# RK3399_Side_of_LPDDR4_Controller.net
KiCad netlist of a schematic drawn in Altium Designer
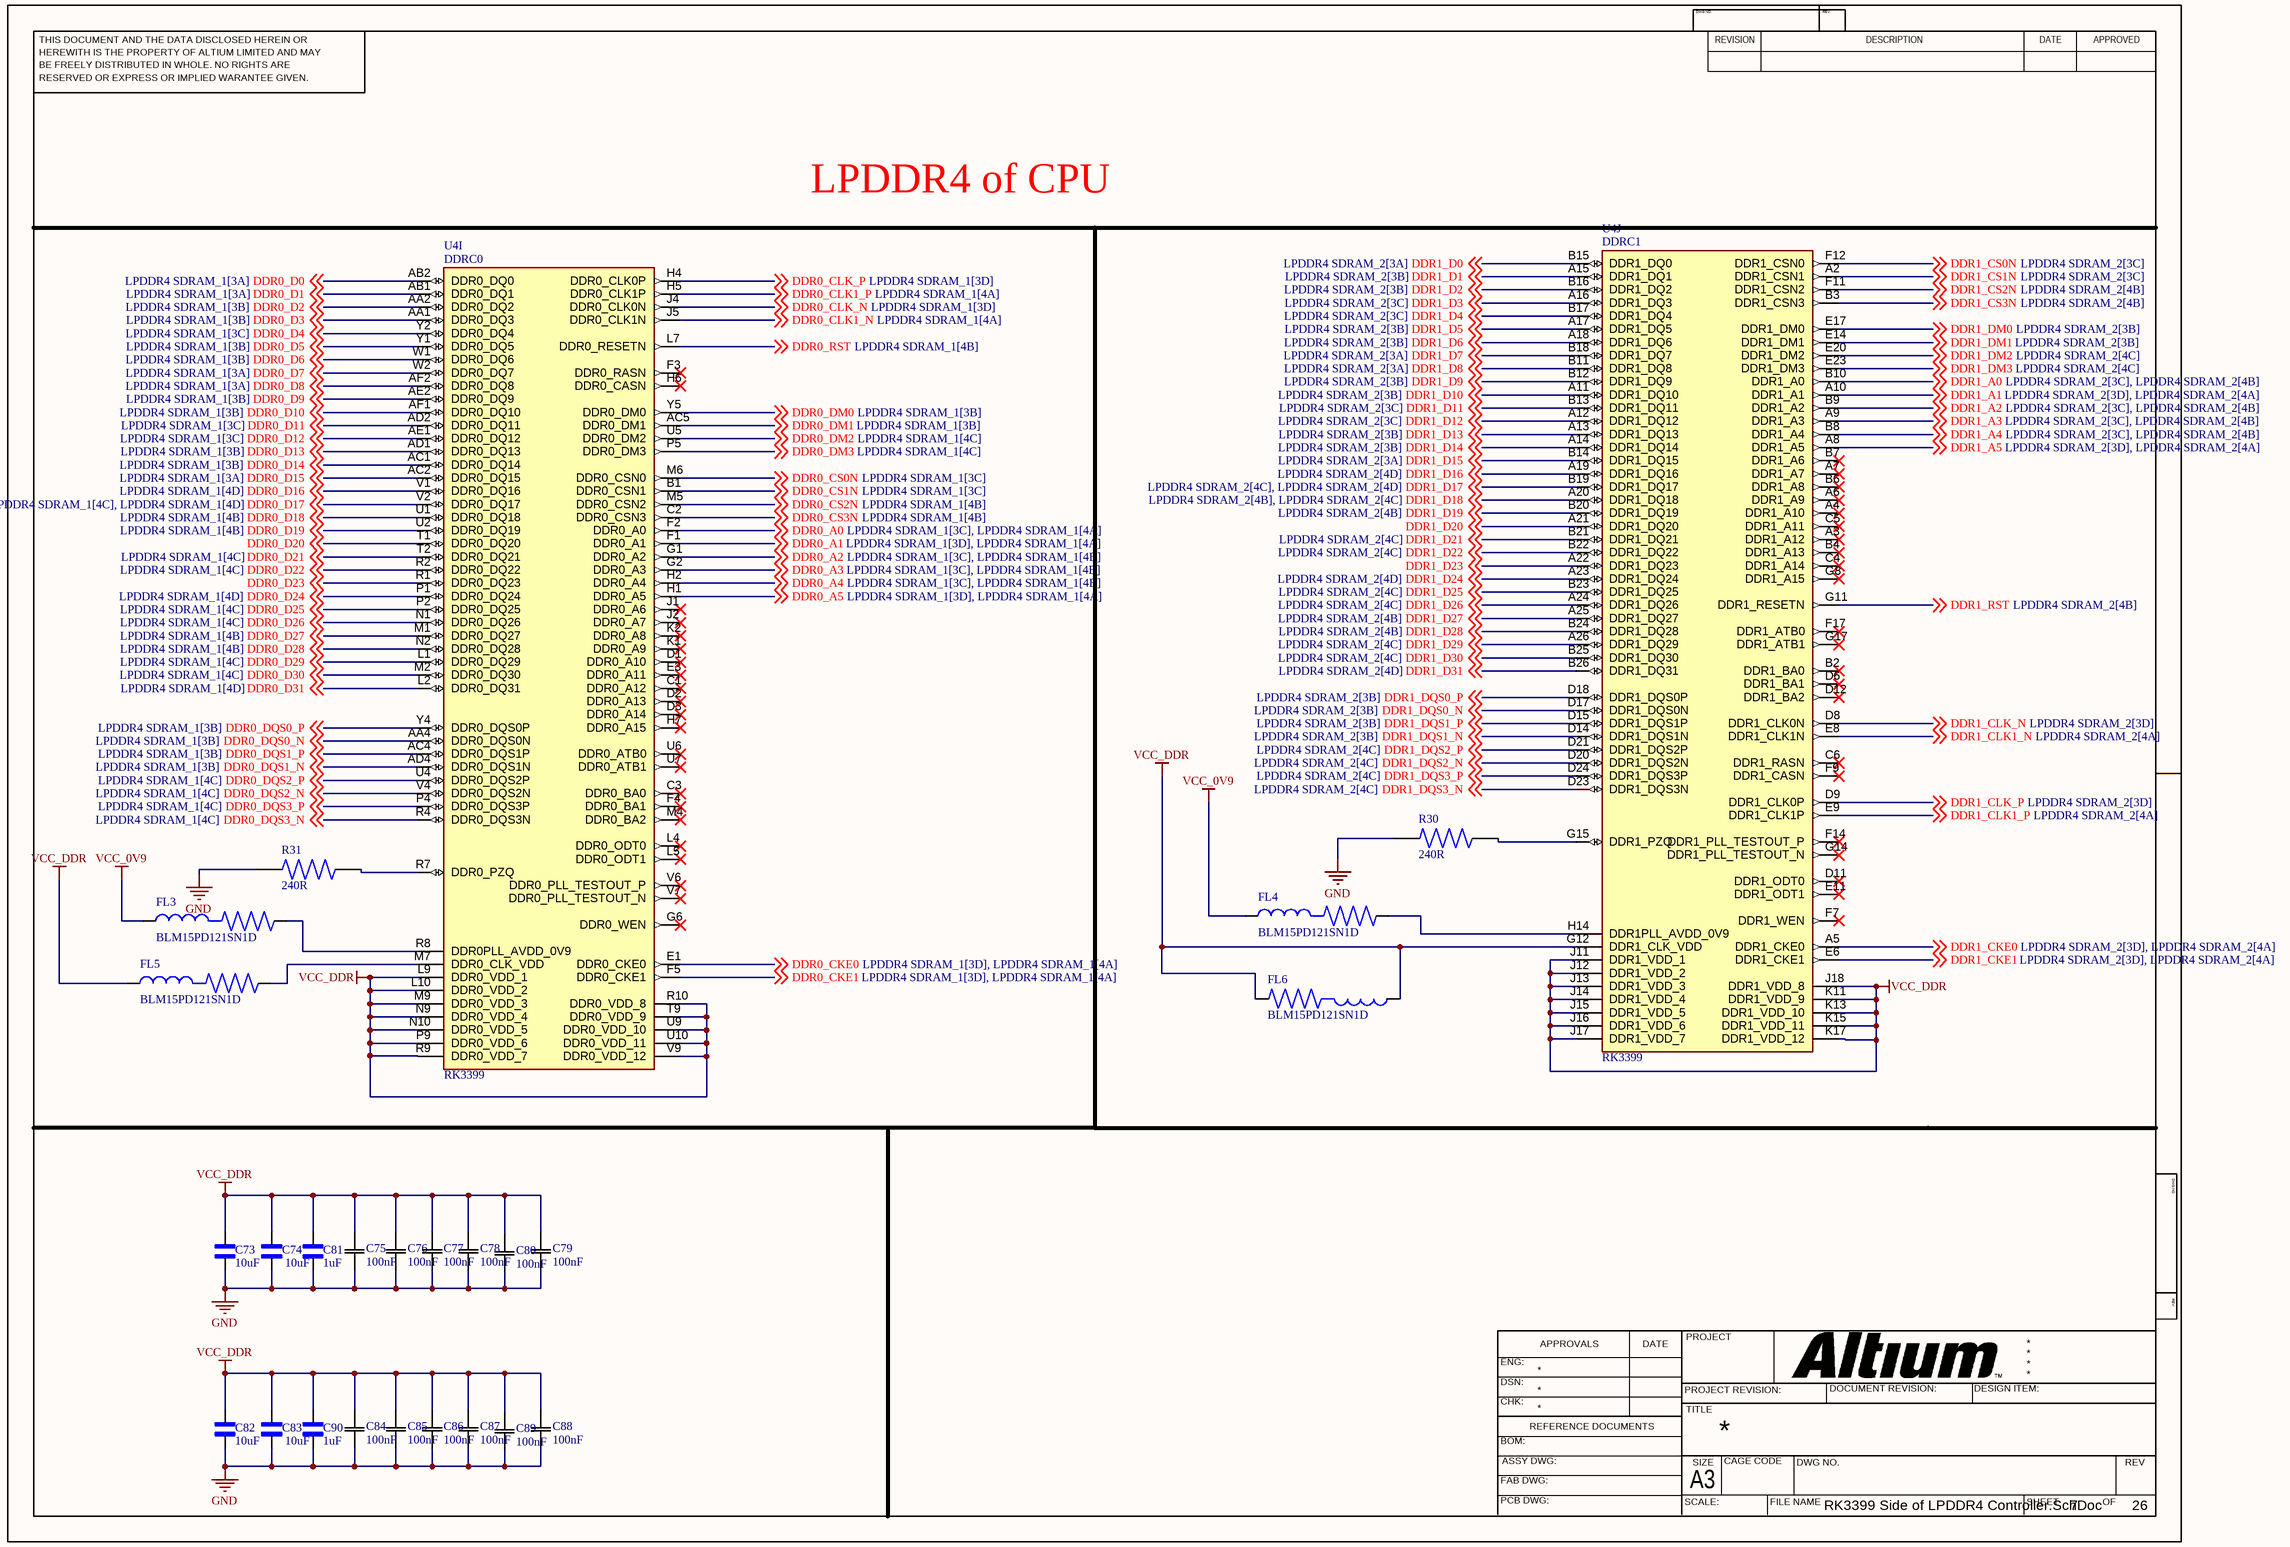
[diagram p0: RK3399 Side of LPDDR4 Controller.SchDoc]

(export (version "E")
  (design (tool "Eeschema 10.0.6"))
  (components
    (comp (ref "C73")
      (value "10uF")
      (footprint "CAPC1005X71N")
      (description "22 ÂµF Â±20% 6.3V Ceramic Capacitor X5R 0402 (1005 Metric)")
      (fields (field (name "MF") "AVX") (field (name "MP") "04026D226MAT2A"))
      (libsource (lib "04026D226MAT2A") (part "04026D226MAT2A"))
    )
    (comp (ref "C74")
      (value "10uF")
      (footprint "CAPC1005X70N")
      (description "10 ÂµF Â±20% 6.3V Ceramic Capacitor X5R 0402 (1005 Metric)")
      (fields (field (name "MF") "Samsung") (field (name "MP") "CL05A106MQ5NUNC"))
      (libsource (lib "CL05A106MQ5NUNC") (part "CL05A106MQ5NUNC"))
    )
    (comp (ref "C75")
      (value "100nF")
      (footprint "CAP_1005_TDK")
      (description "Description")
      (fields
        (field (name "MANUFACTURER_PART_NUMBER") "C1005X7R1H104M050BB")
        (field (name "COPYRIGHT") "Copyright (C) 2025 Ultra Librarian. All rights reserved.")
      )
      (libsource (lib "C1005X7R1H104M050BB") (part "C1005X7R1H104M050BB"))
    )
    (comp (ref "C76")
      (value "100nF")
      (footprint "CAP_1005_TDK")
      (description "Description")
      (fields
        (field (name "MANUFACTURER_PART_NUMBER") "C1005X7R1H104M050BB")
        (field (name "COPYRIGHT") "Copyright (C) 2025 Ultra Librarian. All rights reserved.")
      )
      (libsource (lib "C1005X7R1H104M050BB") (part "C1005X7R1H104M050BB"))
    )
    (comp (ref "C77")
      (value "100nF")
      (footprint "CAP_1005_TDK")
      (description "Description")
      (fields
        (field (name "MANUFACTURER_PART_NUMBER") "C1005X7R1H104M050BB")
        (field (name "COPYRIGHT") "Copyright (C) 2025 Ultra Librarian. All rights reserved.")
      )
      (libsource (lib "C1005X7R1H104M050BB") (part "C1005X7R1H104M050BB"))
    )
    (comp (ref "C78")
      (value "100nF")
      (footprint "CAP_1005_TDK")
      (description "Description")
      (fields
        (field (name "MANUFACTURER_PART_NUMBER") "C1005X7R1H104M050BB")
        (field (name "COPYRIGHT") "Copyright (C) 2025 Ultra Librarian. All rights reserved.")
      )
      (libsource (lib "C1005X7R1H104M050BB") (part "C1005X7R1H104M050BB"))
    )
    (comp (ref "C79")
      (value "100nF")
      (footprint "CAP_1005_TDK")
      (description "Description")
      (fields
        (field (name "MANUFACTURER_PART_NUMBER") "C1005X7R1H104M050BB")
        (field (name "COPYRIGHT") "Copyright (C) 2025 Ultra Librarian. All rights reserved.")
      )
      (libsource (lib "C1005X7R1H104M050BB") (part "C1005X7R1H104M050BB"))
    )
    (comp (ref "C80")
      (value "100nF")
      (footprint "CAP_1005_TDK")
      (description "Description")
      (fields
        (field (name "MANUFACTURER_PART_NUMBER") "C1005X7R1H104M050BB")
        (field (name "COPYRIGHT") "Copyright (C) 2025 Ultra Librarian. All rights reserved.")
      )
      (libsource (lib "C1005X7R1H104M050BB") (part "C1005X7R1H104M050BB"))
    )
    (comp (ref "C81")
      (value "1uF")
      (footprint "CAPC1005X56N")
      (description "1 ÂµF Â±10% 10V Ceramic Capacitor X5R 0402 (1005 Metric)")
      (fields (field (name "MF") "AVX") (field (name "MP") "0402ZD105KAT4A"))
      (libsource (lib "0402ZD105KAT4A") (part "0402ZD105KAT4A"))
    )
    (comp (ref "C82")
      (value "10uF")
      (footprint "CAPC1005X71N")
      (description "22 ÂµF Â±20% 6.3V Ceramic Capacitor X5R 0402 (1005 Metric)")
      (fields (field (name "MF") "AVX") (field (name "MP") "04026D226MAT2A"))
      (libsource (lib "04026D226MAT2A") (part "04026D226MAT2A"))
    )
    (comp (ref "C83")
      (value "10uF")
      (footprint "CAPC1005X70N")
      (description "10 ÂµF Â±20% 6.3V Ceramic Capacitor X5R 0402 (1005 Metric)")
      (fields (field (name "MF") "Samsung") (field (name "MP") "CL05A106MQ5NUNC"))
      (libsource (lib "CL05A106MQ5NUNC") (part "CL05A106MQ5NUNC"))
    )
    (comp (ref "C84")
      (value "100nF")
      (footprint "CAP_1005_TDK")
      (description "Description")
      (fields
        (field (name "MANUFACTURER_PART_NUMBER") "C1005X7R1H104M050BB")
        (field (name "COPYRIGHT") "Copyright (C) 2025 Ultra Librarian. All rights reserved.")
      )
      (libsource (lib "C1005X7R1H104M050BB") (part "C1005X7R1H104M050BB"))
    )
    (comp (ref "C85")
      (value "100nF")
      (footprint "CAP_1005_TDK")
      (description "Description")
      (fields
        (field (name "MANUFACTURER_PART_NUMBER") "C1005X7R1H104M050BB")
        (field (name "COPYRIGHT") "Copyright (C) 2025 Ultra Librarian. All rights reserved.")
      )
      (libsource (lib "C1005X7R1H104M050BB") (part "C1005X7R1H104M050BB"))
    )
    (comp (ref "C86")
      (value "100nF")
      (footprint "CAP_1005_TDK")
      (description "Description")
      (fields
        (field (name "MANUFACTURER_PART_NUMBER") "C1005X7R1H104M050BB")
        (field (name "COPYRIGHT") "Copyright (C) 2025 Ultra Librarian. All rights reserved.")
      )
      (libsource (lib "C1005X7R1H104M050BB") (part "C1005X7R1H104M050BB"))
    )
    (comp (ref "C87")
      (value "100nF")
      (footprint "CAP_1005_TDK")
      (description "Description")
      (fields
        (field (name "MANUFACTURER_PART_NUMBER") "C1005X7R1H104M050BB")
        (field (name "COPYRIGHT") "Copyright (C) 2025 Ultra Librarian. All rights reserved.")
      )
      (libsource (lib "C1005X7R1H104M050BB") (part "C1005X7R1H104M050BB"))
    )
    (comp (ref "C88")
      (value "100nF")
      (footprint "CAP_1005_TDK")
      (description "Description")
      (fields
        (field (name "MANUFACTURER_PART_NUMBER") "C1005X7R1H104M050BB")
        (field (name "COPYRIGHT") "Copyright (C) 2025 Ultra Librarian. All rights reserved.")
      )
      (libsource (lib "C1005X7R1H104M050BB") (part "C1005X7R1H104M050BB"))
    )
    (comp (ref "C89")
      (value "100nF")
      (footprint "CAP_1005_TDK")
      (description "Description")
      (fields
        (field (name "MANUFACTURER_PART_NUMBER") "C1005X7R1H104M050BB")
        (field (name "COPYRIGHT") "Copyright (C) 2025 Ultra Librarian. All rights reserved.")
      )
      (libsource (lib "C1005X7R1H104M050BB") (part "C1005X7R1H104M050BB"))
    )
    (comp (ref "C90")
      (value "1uF")
      (footprint "CAPC1005X56N")
      (description "1 ÂµF Â±10% 10V Ceramic Capacitor X5R 0402 (1005 Metric)")
      (fields (field (name "MF") "AVX") (field (name "MP") "0402ZD105KAT4A"))
      (libsource (lib "0402ZD105KAT4A") (part "0402ZD105KAT4A"))
    )
    (comp (ref "FL3")
      (value "BLM15PD121SN1D")
      (footprint "BEADC1005X55N")
      (description "120 Ohms @ 100 MHz 1 Power Line Ferrite Bead 0402 (1005 Metric) 1.3A 90mOhm")
      (fields (field (name "MF") "Murata"))
      (libsource (lib "BLM15PD121SN1D") (part "BLM15PD121SN1D"))
    )
    (comp (ref "FL4")
      (value "BLM15PD121SN1D")
      (footprint "BEADC1005X55N")
      (description "120 Ohms @ 100 MHz 1 Power Line Ferrite Bead 0402 (1005 Metric) 1.3A 90mOhm")
      (fields (field (name "MF") "Murata"))
      (libsource (lib "BLM15PD121SN1D") (part "BLM15PD121SN1D"))
    )
    (comp (ref "FL5")
      (value "BLM15PD121SN1D")
      (footprint "BEADC1005X55N")
      (description "120 Ohms @ 100 MHz 1 Power Line Ferrite Bead 0402 (1005 Metric) 1.3A 90mOhm")
      (fields (field (name "MF") "Murata"))
      (libsource (lib "BLM15PD121SN1D") (part "BLM15PD121SN1D"))
    )
    (comp (ref "FL6")
      (value "BLM15PD121SN1D")
      (footprint "BEADC1005X55N")
      (description "120 Ohms @ 100 MHz 1 Power Line Ferrite Bead 0402 (1005 Metric) 1.3A 90mOhm")
      (fields (field (name "MF") "Murata"))
      (libsource (lib "BLM15PD121SN1D") (part "BLM15PD121SN1D"))
    )
    (comp (ref "R30")
      (value "240R")
      (footprint "RES_ERJP08F1101V")
      (fields (field (name "MP") "ERA6AED241V"))
      (libsource (lib "ERA6AED241V") (part "ERA6AED241V"))
    )
    (comp (ref "R31")
      (value "240R")
      (footprint "RESC1608X50N")
      (fields (field (name "MP") "ERA6AED241V"))
      (libsource (lib "ERA6AED241V") (part "ERA6AED241V"))
    )
    (comp (ref "U4")
      (value "RK3399")
      (footprint "BGA828C65P31X31_2100X2100X161N")
      (description "RK3399 ROCK Pi 4 Model A 2GB - ARMÂ® CortexÂ®-A53, CortexÂ®-A72 MPU Embedded Evaluation Board")
      (fields (field (name "MF") "Rockchip"))
      (libsource (lib "RK3399") (part "RK3399"))
    )
  )
  (nets
    (net (code "1") (name "DDR0_A0") (class "Default")
      (node (ref "U4") (pin "F2") (pinfunction "DDR0_A0_F2") (pintype "output"))
    )
    (net (code "2") (name "DDR0_A1") (class "Default")
      (node (ref "U4") (pin "F1") (pinfunction "DDR0_A1_F1") (pintype "output"))
    )
    (net (code "3") (name "DDR0_A2") (class "Default")
      (node (ref "U4") (pin "G1") (pinfunction "DDR0_A2_G1") (pintype "output"))
    )
    (net (code "4") (name "DDR0_A3") (class "Default")
      (node (ref "U4") (pin "G2") (pinfunction "DDR0_A3_G2") (pintype "output"))
    )
    (net (code "5") (name "DDR0_A4") (class "Default")
      (node (ref "U4") (pin "H2") (pinfunction "DDR0_A4_H2") (pintype "output"))
    )
    (net (code "6") (name "DDR0_A5") (class "Default")
      (node (ref "U4") (pin "H1") (pinfunction "DDR0_A5_H1") (pintype "output"))
    )
    (net (code "7") (name "DDR0_CKE0") (class "Default")
      (node (ref "U4") (pin "E1") (pinfunction "DDR0_CKE0_E1") (pintype "output"))
    )
    (net (code "8") (name "DDR0_CKE1") (class "Default")
      (node (ref "U4") (pin "F5") (pinfunction "DDR0_CKE1_F5") (pintype "output"))
    )
    (net (code "9") (name "DDR0_CLK1_N") (class "Default")
      (node (ref "U4") (pin "J5") (pinfunction "DDR0_CLK1N_J5") (pintype "output"))
    )
    (net (code "10") (name "DDR0_CLK1_P") (class "Default")
      (node (ref "U4") (pin "H5") (pinfunction "DDR0_CLK1P_H5") (pintype "output"))
    )
    (net (code "11") (name "DDR0_CLK_N") (class "Default")
      (node (ref "U4") (pin "J4") (pinfunction "DDR0_CLK0N_J4") (pintype "output"))
    )
    (net (code "12") (name "DDR0_CLK_P") (class "Default")
      (node (ref "U4") (pin "H4") (pinfunction "DDR0_CLK0P_H4") (pintype "output"))
    )
    (net (code "13") (name "DDR0_CS0N") (class "Default")
      (node (ref "U4") (pin "M6") (pinfunction "DDR0_CSN0_M6") (pintype "output"))
    )
    (net (code "14") (name "DDR0_CS1N") (class "Default")
      (node (ref "U4") (pin "B1") (pinfunction "DDR0_CSN1_B1") (pintype "output"))
    )
    (net (code "15") (name "DDR0_CS2N") (class "Default")
      (node (ref "U4") (pin "M5") (pinfunction "DDR0_CSN2_M5") (pintype "output"))
    )
    (net (code "16") (name "DDR0_CS3N") (class "Default")
      (node (ref "U4") (pin "C2") (pinfunction "DDR0_CSN3_C2") (pintype "output"))
    )
    (net (code "17") (name "DDR0_D0") (class "Default")
      (node (ref "U4") (pin "AB2") (pinfunction "DDR0_DQ0_AB2") (pintype "bidirectional"))
    )
    (net (code "18") (name "DDR0_D1") (class "Default")
      (node (ref "U4") (pin "AB1") (pinfunction "DDR0_DQ1_AB1") (pintype "bidirectional"))
    )
    (net (code "19") (name "DDR0_D2") (class "Default")
      (node (ref "U4") (pin "AA2") (pinfunction "DDR0_DQ2_AA2") (pintype "bidirectional"))
    )
    (net (code "20") (name "DDR0_D3") (class "Default")
      (node (ref "U4") (pin "AA1") (pinfunction "DDR0_DQ3_AA1") (pintype "bidirectional"))
    )
    (net (code "21") (name "DDR0_D4") (class "Default")
      (node (ref "U4") (pin "Y2") (pinfunction "DDR0_DQ4_Y2") (pintype "bidirectional"))
    )
    (net (code "22") (name "DDR0_D5") (class "Default")
      (node (ref "U4") (pin "Y1") (pinfunction "DDR0_DQ5_Y1") (pintype "bidirectional"))
    )
    (net (code "23") (name "DDR0_D6") (class "Default")
      (node (ref "U4") (pin "W1") (pinfunction "DDR0_DQ6_W1") (pintype "bidirectional"))
    )
    (net (code "24") (name "DDR0_D7") (class "Default")
      (node (ref "U4") (pin "W2") (pinfunction "DDR0_DQ7_W2") (pintype "bidirectional"))
    )
    (net (code "25") (name "DDR0_D8") (class "Default")
      (node (ref "U4") (pin "AF2") (pinfunction "DDR0_DQ8_AF2") (pintype "bidirectional"))
    )
    (net (code "26") (name "DDR0_D9") (class "Default")
      (node (ref "U4") (pin "AE2") (pinfunction "DDR0_DQ9_AE2") (pintype "bidirectional"))
    )
    (net (code "27") (name "DDR0_D10") (class "Default")
      (node (ref "U4") (pin "AF1") (pinfunction "DDR0_DQ10_AF1") (pintype "bidirectional"))
    )
    (net (code "28") (name "DDR0_D11") (class "Default")
      (node (ref "U4") (pin "AD2") (pinfunction "DDR0_DQ11_AD2") (pintype "bidirectional"))
    )
    (net (code "29") (name "DDR0_D12") (class "Default")
      (node (ref "U4") (pin "AE1") (pinfunction "DDR0_DQ12_AE1") (pintype "bidirectional"))
    )
    (net (code "30") (name "DDR0_D13") (class "Default")
      (node (ref "U4") (pin "AD1") (pinfunction "DDR0_DQ13_AD1") (pintype "bidirectional"))
    )
    (net (code "31") (name "DDR0_D14") (class "Default")
      (node (ref "U4") (pin "AC1") (pinfunction "DDR0_DQ14_AC1") (pintype "bidirectional"))
    )
    (net (code "32") (name "DDR0_D15") (class "Default")
      (node (ref "U4") (pin "AC2") (pinfunction "DDR0_DQ15_AC2") (pintype "bidirectional"))
    )
    (net (code "33") (name "DDR0_D16") (class "Default")
      (node (ref "U4") (pin "V1") (pinfunction "DDR0_DQ16_V1") (pintype "bidirectional"))
    )
    (net (code "34") (name "DDR0_D17") (class "Default")
      (node (ref "U4") (pin "V2") (pinfunction "DDR0_DQ17_V2") (pintype "bidirectional"))
    )
    (net (code "35") (name "DDR0_D18") (class "Default")
      (node (ref "U4") (pin "U1") (pinfunction "DDR0_DQ18_U1") (pintype "bidirectional"))
    )
    (net (code "36") (name "DDR0_D19") (class "Default")
      (node (ref "U4") (pin "U2") (pinfunction "DDR0_DQ19_U2") (pintype "bidirectional"))
    )
    (net (code "37") (name "DDR0_D20") (class "Default")
      (node (ref "U4") (pin "T1") (pinfunction "DDR0_DQ20_T1") (pintype "bidirectional"))
    )
    (net (code "38") (name "DDR0_D21") (class "Default")
      (node (ref "U4") (pin "T2") (pinfunction "DDR0_DQ21_T2") (pintype "bidirectional"))
    )
    (net (code "39") (name "DDR0_D22") (class "Default")
      (node (ref "U4") (pin "R2") (pinfunction "DDR0_DQ22_R2") (pintype "bidirectional"))
    )
    (net (code "40") (name "DDR0_D23") (class "Default")
      (node (ref "U4") (pin "R1") (pinfunction "DDR0_DQ23_R1") (pintype "bidirectional"))
    )
    (net (code "41") (name "DDR0_D24") (class "Default")
      (node (ref "U4") (pin "P1") (pinfunction "DDR0_DQ24_P1") (pintype "bidirectional"))
    )
    (net (code "42") (name "DDR0_D25") (class "Default")
      (node (ref "U4") (pin "P2") (pinfunction "DDR0_DQ25_P2") (pintype "bidirectional"))
    )
    (net (code "43") (name "DDR0_D26") (class "Default")
      (node (ref "U4") (pin "N1") (pinfunction "DDR0_DQ26_N1") (pintype "bidirectional"))
    )
    (net (code "44") (name "DDR0_D27") (class "Default")
      (node (ref "U4") (pin "M1") (pinfunction "DDR0_DQ27_M1") (pintype "bidirectional"))
    )
    (net (code "45") (name "DDR0_D28") (class "Default")
      (node (ref "U4") (pin "N2") (pinfunction "DDR0_DQ28_N2") (pintype "bidirectional"))
    )
    (net (code "46") (name "DDR0_D29") (class "Default")
      (node (ref "U4") (pin "L1") (pinfunction "DDR0_DQ29_L1") (pintype "bidirectional"))
    )
    (net (code "47") (name "DDR0_D30") (class "Default")
      (node (ref "U4") (pin "M2") (pinfunction "DDR0_DQ30_M2") (pintype "bidirectional"))
    )
    (net (code "48") (name "DDR0_D31") (class "Default")
      (node (ref "U4") (pin "L2") (pinfunction "DDR0_DQ31_L2") (pintype "bidirectional"))
    )
    (net (code "49") (name "DDR0_DM0") (class "Default")
      (node (ref "U4") (pin "Y5") (pinfunction "DDR0_DM0_Y5") (pintype "output"))
    )
    (net (code "50") (name "DDR0_DM1") (class "Default")
      (node (ref "U4") (pin "AC5") (pinfunction "DDR0_DM1_AC5") (pintype "output"))
    )
    (net (code "51") (name "DDR0_DM2") (class "Default")
      (node (ref "U4") (pin "U5") (pinfunction "DDR0_DM2_U5") (pintype "output"))
    )
    (net (code "52") (name "DDR0_DM3") (class "Default")
      (node (ref "U4") (pin "P5") (pinfunction "DDR0_DM3_P5") (pintype "output"))
    )
    (net (code "53") (name "DDR0_DQS0_N") (class "Default")
      (node (ref "U4") (pin "AA4") (pinfunction "DDR0_DQS0N_AA4") (pintype "bidirectional"))
    )
    (net (code "54") (name "DDR0_DQS0_P") (class "Default")
      (node (ref "U4") (pin "Y4") (pinfunction "DDR0_DQS0P_Y4") (pintype "bidirectional"))
    )
    (net (code "55") (name "DDR0_DQS1_N") (class "Default")
      (node (ref "U4") (pin "AD4") (pinfunction "DDR0_DQS1N_AD4") (pintype "bidirectional"))
    )
    (net (code "56") (name "DDR0_DQS1_P") (class "Default")
      (node (ref "U4") (pin "AC4") (pinfunction "DDR0_DQS1P_AC4") (pintype "bidirectional"))
    )
    (net (code "57") (name "DDR0_DQS2_N") (class "Default")
      (node (ref "U4") (pin "V4") (pinfunction "DDR0_DQS2N_V4") (pintype "bidirectional"))
    )
    (net (code "58") (name "DDR0_DQS2_P") (class "Default")
      (node (ref "U4") (pin "U4") (pinfunction "DDR0_DQS2P_U4") (pintype "bidirectional"))
    )
    (net (code "59") (name "DDR0_DQS3_N") (class "Default")
      (node (ref "U4") (pin "R4") (pinfunction "DDR0_DQS3N_R4") (pintype "bidirectional"))
    )
    (net (code "60") (name "DDR0_DQS3_P") (class "Default")
      (node (ref "U4") (pin "P4") (pinfunction "DDR0_DQS3P_P4") (pintype "bidirectional"))
    )
    (net (code "61") (name "DDR0_RST") (class "Default")
      (node (ref "U4") (pin "L7") (pinfunction "DDR0_RESETN_L7") (pintype "output"))
    )
    (net (code "62") (name "DDR1_A0") (class "Default")
      (node (ref "U4") (pin "B10") (pinfunction "DDR1_A0_B10") (pintype "output"))
    )
    (net (code "63") (name "DDR1_A1") (class "Default")
      (node (ref "U4") (pin "A10") (pinfunction "DDR1_A1_A10") (pintype "output"))
    )
    (net (code "64") (name "DDR1_A2") (class "Default")
      (node (ref "U4") (pin "B9") (pinfunction "DDR1_A2_B9") (pintype "output"))
    )
    (net (code "65") (name "DDR1_A3") (class "Default")
      (node (ref "U4") (pin "A9") (pinfunction "DDR1_A3_A9") (pintype "output"))
    )
    (net (code "66") (name "DDR1_A4") (class "Default")
      (node (ref "U4") (pin "B8") (pinfunction "DDR1_A4_B8") (pintype "output"))
    )
    (net (code "67") (name "DDR1_A5") (class "Default")
      (node (ref "U4") (pin "A8") (pinfunction "DDR1_A5_A8") (pintype "output"))
    )
    (net (code "68") (name "DDR1_CKE0") (class "Default")
      (node (ref "U4") (pin "A5") (pinfunction "DDR1_CKE0_A5") (pintype "output"))
    )
    (net (code "69") (name "DDR1_CKE1") (class "Default")
      (node (ref "U4") (pin "E6") (pinfunction "DDR1_CKE1_E6") (pintype "output"))
    )
    (net (code "70") (name "DDR1_CLK1_N") (class "Default")
      (node (ref "U4") (pin "E8") (pinfunction "DDR1_CLK1N_E8") (pintype "output"))
    )
    (net (code "71") (name "DDR1_CLK1_P") (class "Default")
      (node (ref "U4") (pin "E9") (pinfunction "DDR1_CLK1P_E9") (pintype "output"))
    )
    (net (code "72") (name "DDR1_CLK_N") (class "Default")
      (node (ref "U4") (pin "D8") (pinfunction "DDR1_CLK0N_D8") (pintype "output"))
    )
    (net (code "73") (name "DDR1_CLK_P") (class "Default")
      (node (ref "U4") (pin "D9") (pinfunction "DDR1_CLK0P_D9") (pintype "output"))
    )
    (net (code "74") (name "DDR1_CS0N") (class "Default")
      (node (ref "U4") (pin "F12") (pinfunction "DDR1_CSN0_F12") (pintype "output"))
    )
    (net (code "75") (name "DDR1_CS1N") (class "Default")
      (node (ref "U4") (pin "A2") (pinfunction "DDR1_CSN1_A2") (pintype "output"))
    )
    (net (code "76") (name "DDR1_CS2N") (class "Default")
      (node (ref "U4") (pin "F11") (pinfunction "DDR1_CSN2_F11") (pintype "output"))
    )
    (net (code "77") (name "DDR1_CS3N") (class "Default")
      (node (ref "U4") (pin "B3") (pinfunction "DDR1_CSN3_B3") (pintype "output"))
    )
    (net (code "78") (name "DDR1_D0") (class "Default")
      (node (ref "U4") (pin "B15") (pinfunction "DDR1_DQ0_B15") (pintype "bidirectional"))
    )
    (net (code "79") (name "DDR1_D1") (class "Default")
      (node (ref "U4") (pin "A15") (pinfunction "DDR1_DQ1_A15") (pintype "bidirectional"))
    )
    (net (code "80") (name "DDR1_D2") (class "Default")
      (node (ref "U4") (pin "B16") (pinfunction "DDR1_DQ2_B16") (pintype "bidirectional"))
    )
    (net (code "81") (name "DDR1_D3") (class "Default")
      (node (ref "U4") (pin "A16") (pinfunction "DDR1_DQ3_A16") (pintype "bidirectional"))
    )
    (net (code "82") (name "DDR1_D4") (class "Default")
      (node (ref "U4") (pin "B17") (pinfunction "DDR1_DQ4_B17") (pintype "bidirectional"))
    )
    (net (code "83") (name "DDR1_D5") (class "Default")
      (node (ref "U4") (pin "A17") (pinfunction "DDR1_DQ5_A17") (pintype "bidirectional"))
    )
    (net (code "84") (name "DDR1_D6") (class "Default")
      (node (ref "U4") (pin "A18") (pinfunction "DDR1_DQ6_A18") (pintype "bidirectional"))
    )
    (net (code "85") (name "DDR1_D7") (class "Default")
      (node (ref "U4") (pin "B18") (pinfunction "DDR1_DQ7_B18") (pintype "bidirectional"))
    )
    (net (code "86") (name "DDR1_D8") (class "Default")
      (node (ref "U4") (pin "B11") (pinfunction "DDR1_DQ8_B11") (pintype "bidirectional"))
    )
    (net (code "87") (name "DDR1_D9") (class "Default")
      (node (ref "U4") (pin "B12") (pinfunction "DDR1_DQ9_B12") (pintype "bidirectional"))
    )
    (net (code "88") (name "DDR1_D10") (class "Default")
      (node (ref "U4") (pin "A11") (pinfunction "DDR1_DQ10_A11") (pintype "bidirectional"))
    )
    (net (code "89") (name "DDR1_D11") (class "Default")
      (node (ref "U4") (pin "B13") (pinfunction "DDR1_DQ11_B13") (pintype "bidirectional"))
    )
    (net (code "90") (name "DDR1_D12") (class "Default")
      (node (ref "U4") (pin "A12") (pinfunction "DDR1_DQ12_A12") (pintype "bidirectional"))
    )
    (net (code "91") (name "DDR1_D13") (class "Default")
      (node (ref "U4") (pin "A13") (pinfunction "DDR1_DQ13_A13") (pintype "bidirectional"))
    )
    (net (code "92") (name "DDR1_D14") (class "Default")
      (node (ref "U4") (pin "A14") (pinfunction "DDR1_DQ14_A14") (pintype "bidirectional"))
    )
    (net (code "93") (name "DDR1_D15") (class "Default")
      (node (ref "U4") (pin "B14") (pinfunction "DDR1_DQ15_B14") (pintype "bidirectional"))
    )
    (net (code "94") (name "DDR1_D16") (class "Default")
      (node (ref "U4") (pin "A19") (pinfunction "DDR1_DQ16_A19") (pintype "bidirectional"))
    )
    (net (code "95") (name "DDR1_D17") (class "Default")
      (node (ref "U4") (pin "B19") (pinfunction "DDR1_DQ17_B19") (pintype "bidirectional"))
    )
    (net (code "96") (name "DDR1_D18") (class "Default")
      (node (ref "U4") (pin "A20") (pinfunction "DDR1_DQ18_A20") (pintype "bidirectional"))
    )
    (net (code "97") (name "DDR1_D19") (class "Default")
      (node (ref "U4") (pin "B20") (pinfunction "DDR1_DQ19_B20") (pintype "bidirectional"))
    )
    (net (code "98") (name "DDR1_D20") (class "Default")
      (node (ref "U4") (pin "A21") (pinfunction "DDR1_DQ20_A21") (pintype "bidirectional"))
    )
    (net (code "99") (name "DDR1_D21") (class "Default")
      (node (ref "U4") (pin "B21") (pinfunction "DDR1_DQ21_B21") (pintype "bidirectional"))
    )
    (net (code "100") (name "DDR1_D22") (class "Default")
      (node (ref "U4") (pin "B22") (pinfunction "DDR1_DQ22_B22") (pintype "bidirectional"))
    )
    (net (code "101") (name "DDR1_D23") (class "Default")
      (node (ref "U4") (pin "A22") (pinfunction "DDR1_DQ23_A22") (pintype "bidirectional"))
    )
    (net (code "102") (name "DDR1_D24") (class "Default")
      (node (ref "U4") (pin "A23") (pinfunction "DDR1_DQ24_A23") (pintype "bidirectional"))
    )
    (net (code "103") (name "DDR1_D25") (class "Default")
      (node (ref "U4") (pin "B23") (pinfunction "DDR1_DQ25_B23") (pintype "bidirectional"))
    )
    (net (code "104") (name "DDR1_D26") (class "Default")
      (node (ref "U4") (pin "A24") (pinfunction "DDR1_DQ26_A24") (pintype "bidirectional"))
    )
    (net (code "105") (name "DDR1_D27") (class "Default")
      (node (ref "U4") (pin "A25") (pinfunction "DDR1_DQ27_A25") (pintype "bidirectional"))
    )
    (net (code "106") (name "DDR1_D28") (class "Default")
      (node (ref "U4") (pin "B24") (pinfunction "DDR1_DQ28_B24") (pintype "bidirectional"))
    )
    (net (code "107") (name "DDR1_D29") (class "Default")
      (node (ref "U4") (pin "A26") (pinfunction "DDR1_DQ29_A26") (pintype "bidirectional"))
    )
    (net (code "108") (name "DDR1_D30") (class "Default")
      (node (ref "U4") (pin "B25") (pinfunction "DDR1_DQ30_B25") (pintype "bidirectional"))
    )
    (net (code "109") (name "DDR1_D31") (class "Default")
      (node (ref "U4") (pin "B26") (pinfunction "DDR1_DQ31_B26") (pintype "bidirectional"))
    )
    (net (code "110") (name "DDR1_DM0") (class "Default")
      (node (ref "U4") (pin "E17") (pinfunction "DDR1_DM0_E17") (pintype "output"))
    )
    (net (code "111") (name "DDR1_DM1") (class "Default")
      (node (ref "U4") (pin "E14") (pinfunction "DDR1_DM1_E14") (pintype "output"))
    )
    (net (code "112") (name "DDR1_DM2") (class "Default")
      (node (ref "U4") (pin "E20") (pinfunction "DDR1_DM2_E20") (pintype "output"))
    )
    (net (code "113") (name "DDR1_DM3") (class "Default")
      (node (ref "U4") (pin "E23") (pinfunction "DDR1_DM3_E23") (pintype "output"))
    )
    (net (code "114") (name "DDR1_DQS0_N") (class "Default")
      (node (ref "U4") (pin "D17") (pinfunction "DDR1_DQS0N_D17") (pintype "bidirectional"))
    )
    (net (code "115") (name "DDR1_DQS0_P") (class "Default")
      (node (ref "U4") (pin "D18") (pinfunction "DDR1_DQS0P_D18") (pintype "bidirectional"))
    )
    (net (code "116") (name "DDR1_DQS1_N") (class "Default")
      (node (ref "U4") (pin "D14") (pinfunction "DDR1_DQS1N_D14") (pintype "bidirectional"))
    )
    (net (code "117") (name "DDR1_DQS1_P") (class "Default")
      (node (ref "U4") (pin "D15") (pinfunction "DDR1_DQS1P_D15") (pintype "bidirectional"))
    )
    (net (code "118") (name "DDR1_DQS2_N") (class "Default")
      (node (ref "U4") (pin "D20") (pinfunction "DDR1_DQS2N_D20") (pintype "bidirectional"))
    )
    (net (code "119") (name "DDR1_DQS2_P") (class "Default")
      (node (ref "U4") (pin "D21") (pinfunction "DDR1_DQS2P_D21") (pintype "bidirectional"))
    )
    (net (code "120") (name "DDR1_DQS3_N") (class "Default")
      (node (ref "U4") (pin "D23") (pinfunction "DDR1_DQS3N_D23") (pintype "bidirectional"))
    )
    (net (code "121") (name "DDR1_DQS3_P") (class "Default")
      (node (ref "U4") (pin "D24") (pinfunction "DDR1_DQS3P_D24") (pintype "bidirectional"))
    )
    (net (code "122") (name "DDR1_RST") (class "Default")
      (node (ref "U4") (pin "G11") (pinfunction "DDR1_RESETN_G11") (pintype "output"))
    )
    (net (code "123") (name "GND") (class "Default")
      (node (ref "C73") (pin "1") (pinfunction "1_1") (pintype "passive"))
      (node (ref "C74") (pin "1") (pinfunction "1_1") (pintype "passive"))
      (node (ref "C75") (pin "1") (pinfunction "1_1") (pintype "passive"))
      (node (ref "C76") (pin "1") (pinfunction "1_1") (pintype "passive"))
      (node (ref "C77") (pin "1") (pinfunction "1_1") (pintype "passive"))
      (node (ref "C78") (pin "1") (pinfunction "1_1") (pintype "passive"))
      (node (ref "C79") (pin "1") (pinfunction "1_1") (pintype "passive"))
      (node (ref "C80") (pin "1") (pinfunction "1_1") (pintype "passive"))
      (node (ref "C81") (pin "1") (pinfunction "1_1") (pintype "passive"))
      (node (ref "C82") (pin "1") (pinfunction "1_1") (pintype "passive"))
      (node (ref "C83") (pin "1") (pinfunction "1_1") (pintype "passive"))
      (node (ref "C84") (pin "1") (pinfunction "1_1") (pintype "passive"))
      (node (ref "C85") (pin "1") (pinfunction "1_1") (pintype "passive"))
      (node (ref "C86") (pin "1") (pinfunction "1_1") (pintype "passive"))
      (node (ref "C87") (pin "1") (pinfunction "1_1") (pintype "passive"))
      (node (ref "C88") (pin "1") (pinfunction "1_1") (pintype "passive"))
      (node (ref "C89") (pin "1") (pinfunction "1_1") (pintype "passive"))
      (node (ref "C90") (pin "1") (pinfunction "1_1") (pintype "passive"))
      (node (ref "R30") (pin "1") (pinfunction "1_1") (pintype "passive"))
      (node (ref "R31") (pin "1") (pinfunction "1_1") (pintype "passive"))
    )
    (net (code "124") (name "Net-(U4I-DDR0PLL_AVDD_0V9)") (class "Default")
      (node (ref "FL3") (pin "2") (pinfunction "2_2") (pintype "passive"))
      (node (ref "U4") (pin "R8") (pinfunction "DDR0PLL_AVDD_0V9_R8") (pintype "power_in"))
    )
    (net (code "125") (name "Net-(U4I-DDR0_CLK_VDD)") (class "Default")
      (node (ref "FL5") (pin "2") (pinfunction "2_2") (pintype "passive"))
      (node (ref "U4") (pin "M7") (pinfunction "DDR0_CLK_VDD_M7") (pintype "power_in"))
    )
    (net (code "126") (name "Net-(U4I-DDR0_PZQ)") (class "Default")
      (node (ref "R31") (pin "2") (pinfunction "2_2") (pintype "passive"))
      (node (ref "U4") (pin "R7") (pinfunction "DDR0_PZQ_R7") (pintype "bidirectional"))
    )
    (net (code "127") (name "Net-(U4J-DDR1PLL_AVDD_0V9)") (class "Default")
      (node (ref "FL4") (pin "2") (pinfunction "2_2") (pintype "passive"))
      (node (ref "U4") (pin "H14") (pinfunction "DDR1PLL_AVDD_0V9_H14") (pintype "power_in"))
    )
    (net (code "128") (name "Net-(U4J-DDR1_PZQ)") (class "Default")
      (node (ref "R30") (pin "2") (pinfunction "2_2") (pintype "passive"))
      (node (ref "U4") (pin "G15") (pinfunction "DDR1_PZQ_G15") (pintype "bidirectional"))
    )
    (net (code "129") (name "VCC_0V9") (class "Default")
      (node (ref "FL3") (pin "1") (pinfunction "1_1") (pintype "passive"))
      (node (ref "FL4") (pin "1") (pinfunction "1_1") (pintype "passive"))
    )
    (net (code "130") (name "VCC_DDR") (class "Default")
      (node (ref "C73") (pin "2") (pinfunction "2_2") (pintype "passive"))
      (node (ref "C74") (pin "2") (pinfunction "2_2") (pintype "passive"))
      (node (ref "C75") (pin "2") (pinfunction "2_2") (pintype "passive"))
      (node (ref "C76") (pin "2") (pinfunction "2_2") (pintype "passive"))
      (node (ref "C77") (pin "2") (pinfunction "2_2") (pintype "passive"))
      (node (ref "C78") (pin "2") (pinfunction "2_2") (pintype "passive"))
      (node (ref "C79") (pin "2") (pinfunction "2_2") (pintype "passive"))
      (node (ref "C80") (pin "2") (pinfunction "2_2") (pintype "passive"))
      (node (ref "C81") (pin "2") (pinfunction "2_2") (pintype "passive"))
      (node (ref "C82") (pin "2") (pinfunction "2_2") (pintype "passive"))
      (node (ref "C83") (pin "2") (pinfunction "2_2") (pintype "passive"))
      (node (ref "C84") (pin "2") (pinfunction "2_2") (pintype "passive"))
      (node (ref "C85") (pin "2") (pinfunction "2_2") (pintype "passive"))
      (node (ref "C86") (pin "2") (pinfunction "2_2") (pintype "passive"))
      (node (ref "C87") (pin "2") (pinfunction "2_2") (pintype "passive"))
      (node (ref "C88") (pin "2") (pinfunction "2_2") (pintype "passive"))
      (node (ref "C89") (pin "2") (pinfunction "2_2") (pintype "passive"))
      (node (ref "C90") (pin "2") (pinfunction "2_2") (pintype "passive"))
      (node (ref "FL5") (pin "1") (pinfunction "1_1") (pintype "passive"))
      (node (ref "FL6") (pin "1") (pinfunction "1_1") (pintype "passive"))
      (node (ref "FL6") (pin "2") (pinfunction "2_2") (pintype "passive"))
      (node (ref "U4") (pin "G12") (pinfunction "DDR1_CLK_VDD_G12") (pintype "power_in"))
      (node (ref "U4") (pin "J11") (pinfunction "DDR1_VDD_1_J11") (pintype "power_in"))
      (node (ref "U4") (pin "J12") (pinfunction "DDR1_VDD_2_J12") (pintype "power_in"))
      (node (ref "U4") (pin "J13") (pinfunction "DDR1_VDD_3_J13") (pintype "power_in"))
      (node (ref "U4") (pin "J14") (pinfunction "DDR1_VDD_4_J14") (pintype "power_in"))
      (node (ref "U4") (pin "J15") (pinfunction "DDR1_VDD_5_J15") (pintype "power_in"))
      (node (ref "U4") (pin "J16") (pinfunction "DDR1_VDD_6_J16") (pintype "power_in"))
      (node (ref "U4") (pin "J17") (pinfunction "DDR1_VDD_7_J17") (pintype "power_in"))
      (node (ref "U4") (pin "J18") (pinfunction "DDR1_VDD_8_J18") (pintype "power_in"))
      (node (ref "U4") (pin "K11") (pinfunction "DDR1_VDD_9_K11") (pintype "power_in"))
      (node (ref "U4") (pin "K13") (pinfunction "DDR1_VDD_10_K13") (pintype "power_in"))
      (node (ref "U4") (pin "K15") (pinfunction "DDR1_VDD_11_K15") (pintype "power_in"))
      (node (ref "U4") (pin "K17") (pinfunction "DDR1_VDD_12_K17") (pintype "power_in"))
      (node (ref "U4") (pin "L10") (pinfunction "DDR0_VDD_2_L10") (pintype "power_in"))
      (node (ref "U4") (pin "L9") (pinfunction "DDR0_VDD_1_L9") (pintype "power_in"))
      (node (ref "U4") (pin "M9") (pinfunction "DDR0_VDD_3_M9") (pintype "power_in"))
      (node (ref "U4") (pin "N10") (pinfunction "DDR0_VDD_5_N10") (pintype "power_in"))
      (node (ref "U4") (pin "N9") (pinfunction "DDR0_VDD_4_N9") (pintype "power_in"))
      (node (ref "U4") (pin "P9") (pinfunction "DDR0_VDD_6_P9") (pintype "power_in"))
      (node (ref "U4") (pin "R10") (pinfunction "DDR0_VDD_8_R10") (pintype "power_in"))
      (node (ref "U4") (pin "R9") (pinfunction "DDR0_VDD_7_R9") (pintype "power_in"))
      (node (ref "U4") (pin "T9") (pinfunction "DDR0_VDD_9_T9") (pintype "power_in"))
      (node (ref "U4") (pin "U10") (pinfunction "DDR0_VDD_11_U10") (pintype "power_in"))
      (node (ref "U4") (pin "U9") (pinfunction "DDR0_VDD_10_U9") (pintype "power_in"))
      (node (ref "U4") (pin "V9") (pinfunction "DDR0_VDD_12_V9") (pintype "power_in"))
    )
    (net (code "131") (name "unconnected-(U4I-DDR0_A6-PadJ1)") (class "Default")
      (node (ref "U4") (pin "J1") (pinfunction "DDR0_A6_J1") (pintype "output+no_connect"))
    )
    (net (code "132") (name "unconnected-(U4I-DDR0_A7-PadJ2)") (class "Default")
      (node (ref "U4") (pin "J2") (pinfunction "DDR0_A7_J2") (pintype "output+no_connect"))
    )
    (net (code "133") (name "unconnected-(U4I-DDR0_A8-PadK2)") (class "Default")
      (node (ref "U4") (pin "K2") (pinfunction "DDR0_A8_K2") (pintype "output+no_connect"))
    )
    (net (code "134") (name "unconnected-(U4I-DDR0_A9-PadK1)") (class "Default")
      (node (ref "U4") (pin "K1") (pinfunction "DDR0_A9_K1") (pintype "output+no_connect"))
    )
    (net (code "135") (name "unconnected-(U4I-DDR0_A10-PadD1)") (class "Default")
      (node (ref "U4") (pin "D1") (pinfunction "DDR0_A10_D1") (pintype "output+no_connect"))
    )
    (net (code "136") (name "unconnected-(U4I-DDR0_A11-PadE3)") (class "Default")
      (node (ref "U4") (pin "E3") (pinfunction "DDR0_A11_E3") (pintype "output+no_connect"))
    )
    (net (code "137") (name "unconnected-(U4I-DDR0_A12-PadC1)") (class "Default")
      (node (ref "U4") (pin "C1") (pinfunction "DDR0_A12_C1") (pintype "output+no_connect"))
    )
    (net (code "138") (name "unconnected-(U4I-DDR0_A13-PadD2)") (class "Default")
      (node (ref "U4") (pin "D2") (pinfunction "DDR0_A13_D2") (pintype "output+no_connect"))
    )
    (net (code "139") (name "unconnected-(U4I-DDR0_A14-PadD3)") (class "Default")
      (node (ref "U4") (pin "D3") (pinfunction "DDR0_A14_D3") (pintype "output+no_connect"))
    )
    (net (code "140") (name "unconnected-(U4I-DDR0_A15-PadH7)") (class "Default")
      (node (ref "U4") (pin "H7") (pinfunction "DDR0_A15_H7") (pintype "output+no_connect"))
    )
    (net (code "141") (name "unconnected-(U4I-DDR0_ATB0-PadU6)") (class "Default")
      (node (ref "U4") (pin "U6") (pinfunction "DDR0_ATB0_U6") (pintype "output+no_connect"))
    )
    (net (code "142") (name "unconnected-(U4I-DDR0_ATB1-PadU7)") (class "Default")
      (node (ref "U4") (pin "U7") (pinfunction "DDR0_ATB1_U7") (pintype "output+no_connect"))
    )
    (net (code "143") (name "unconnected-(U4I-DDR0_BA0-PadC3)") (class "Default")
      (node (ref "U4") (pin "C3") (pinfunction "DDR0_BA0_C3") (pintype "output+no_connect"))
    )
    (net (code "144") (name "unconnected-(U4I-DDR0_BA1-PadF4)") (class "Default")
      (node (ref "U4") (pin "F4") (pinfunction "DDR0_BA1_F4") (pintype "output+no_connect"))
    )
    (net (code "145") (name "unconnected-(U4I-DDR0_BA2-PadM4)") (class "Default")
      (node (ref "U4") (pin "M4") (pinfunction "DDR0_BA2_M4") (pintype "output+no_connect"))
    )
    (net (code "146") (name "unconnected-(U4I-DDR0_CASN-PadH6)") (class "Default")
      (node (ref "U4") (pin "H6") (pinfunction "DDR0_CASN_H6") (pintype "output+no_connect"))
    )
    (net (code "147") (name "unconnected-(U4I-DDR0_ODT0-PadL4)") (class "Default")
      (node (ref "U4") (pin "L4") (pinfunction "DDR0_ODT0_L4") (pintype "output+no_connect"))
    )
    (net (code "148") (name "unconnected-(U4I-DDR0_ODT1-PadL5)") (class "Default")
      (node (ref "U4") (pin "L5") (pinfunction "DDR0_ODT1_L5") (pintype "output+no_connect"))
    )
    (net (code "149") (name "unconnected-(U4I-DDR0_PLL_TESTOUT_N-PadV7)") (class "Default")
      (node (ref "U4") (pin "V7") (pinfunction "DDR0_PLL_TESTOUT_N_V7") (pintype "output+no_connect"))
    )
    (net (code "150") (name "unconnected-(U4I-DDR0_PLL_TESTOUT_P-PadV6)") (class "Default")
      (node (ref "U4") (pin "V6") (pinfunction "DDR0_PLL_TESTOUT_P_V6") (pintype "output+no_connect"))
    )
    (net (code "151") (name "unconnected-(U4I-DDR0_RASN-PadF3)") (class "Default")
      (node (ref "U4") (pin "F3") (pinfunction "DDR0_RASN_F3") (pintype "output+no_connect"))
    )
    (net (code "152") (name "unconnected-(U4I-DDR0_WEN-PadG6)") (class "Default")
      (node (ref "U4") (pin "G6") (pinfunction "DDR0_WEN_G6") (pintype "output+no_connect"))
    )
    (net (code "153") (name "unconnected-(U4J-DDR1_A6-PadB7)") (class "Default")
      (node (ref "U4") (pin "B7") (pinfunction "DDR1_A6_B7") (pintype "output+no_connect"))
    )
    (net (code "154") (name "unconnected-(U4J-DDR1_A7-PadA7)") (class "Default")
      (node (ref "U4") (pin "A7") (pinfunction "DDR1_A7_A7") (pintype "output+no_connect"))
    )
    (net (code "155") (name "unconnected-(U4J-DDR1_A8-PadB6)") (class "Default")
      (node (ref "U4") (pin "B6") (pinfunction "DDR1_A8_B6") (pintype "output+no_connect"))
    )
    (net (code "156") (name "unconnected-(U4J-DDR1_A9-PadA6)") (class "Default")
      (node (ref "U4") (pin "A6") (pinfunction "DDR1_A9_A6") (pintype "output+no_connect"))
    )
    (net (code "157") (name "unconnected-(U4J-DDR1_A10-PadA4)") (class "Default")
      (node (ref "U4") (pin "A4") (pinfunction "DDR1_A10_A4") (pintype "output+no_connect"))
    )
    (net (code "158") (name "unconnected-(U4J-DDR1_A11-PadC5)") (class "Default")
      (node (ref "U4") (pin "C5") (pinfunction "DDR1_A11_C5") (pintype "output+no_connect"))
    )
    (net (code "159") (name "unconnected-(U4J-DDR1_A12-PadA3)") (class "Default")
      (node (ref "U4") (pin "A3") (pinfunction "DDR1_A12_A3") (pintype "output+no_connect"))
    )
    (net (code "160") (name "unconnected-(U4J-DDR1_A13-PadB4)") (class "Default")
      (node (ref "U4") (pin "B4") (pinfunction "DDR1_A13_B4") (pintype "output+no_connect"))
    )
    (net (code "161") (name "unconnected-(U4J-DDR1_A14-PadC4)") (class "Default")
      (node (ref "U4") (pin "C4") (pinfunction "DDR1_A14_C4") (pintype "output+no_connect"))
    )
    (net (code "162") (name "unconnected-(U4J-DDR1_A15-PadG8)") (class "Default")
      (node (ref "U4") (pin "G8") (pinfunction "DDR1_A15_G8") (pintype "output+no_connect"))
    )
    (net (code "163") (name "unconnected-(U4J-DDR1_ATB0-PadF17)") (class "Default")
      (node (ref "U4") (pin "F17") (pinfunction "DDR1_ATB0_F17") (pintype "output+no_connect"))
    )
    (net (code "164") (name "unconnected-(U4J-DDR1_ATB1-PadG17)") (class "Default")
      (node (ref "U4") (pin "G17") (pinfunction "DDR1_ATB1_G17") (pintype "output+no_connect"))
    )
    (net (code "165") (name "unconnected-(U4J-DDR1_BA0-PadB2)") (class "Default")
      (node (ref "U4") (pin "B2") (pinfunction "DDR1_BA0_B2") (pintype "output+no_connect"))
    )
    (net (code "166") (name "unconnected-(U4J-DDR1_BA1-PadD6)") (class "Default")
      (node (ref "U4") (pin "D6") (pinfunction "DDR1_BA1_D6") (pintype "output+no_connect"))
    )
    (net (code "167") (name "unconnected-(U4J-DDR1_BA2-PadD12)") (class "Default")
      (node (ref "U4") (pin "D12") (pinfunction "DDR1_BA2_D12") (pintype "output+no_connect"))
    )
    (net (code "168") (name "unconnected-(U4J-DDR1_CASN-PadF9)") (class "Default")
      (node (ref "U4") (pin "F9") (pinfunction "DDR1_CASN_F9") (pintype "output+no_connect"))
    )
    (net (code "169") (name "unconnected-(U4J-DDR1_ODT0-PadD11)") (class "Default")
      (node (ref "U4") (pin "D11") (pinfunction "DDR1_ODT0_D11") (pintype "output+no_connect"))
    )
    (net (code "170") (name "unconnected-(U4J-DDR1_ODT1-PadE11)") (class "Default")
      (node (ref "U4") (pin "E11") (pinfunction "DDR1_ODT1_E11") (pintype "output+no_connect"))
    )
    (net (code "171") (name "unconnected-(U4J-DDR1_PLL_TESTOUT_N-PadG14)") (class "Default")
      (node (ref "U4") (pin "G14") (pinfunction "DDR1_PLL_TESTOUT_N_G14") (pintype "output+no_connect"))
    )
    (net (code "172") (name "unconnected-(U4J-DDR1_PLL_TESTOUT_P-PadF14)") (class "Default")
      (node (ref "U4") (pin "F14") (pinfunction "DDR1_PLL_TESTOUT_P_F14") (pintype "output+no_connect"))
    )
    (net (code "173") (name "unconnected-(U4J-DDR1_RASN-PadC6)") (class "Default")
      (node (ref "U4") (pin "C6") (pinfunction "DDR1_RASN_C6") (pintype "output+no_connect"))
    )
    (net (code "174") (name "unconnected-(U4J-DDR1_WEN-PadF7)") (class "Default")
      (node (ref "U4") (pin "F7") (pinfunction "DDR1_WEN_F7") (pintype "output+no_connect"))
    )
  )
)
